# Power.net
KiCad netlist of a schematic drawn in Altium Designer
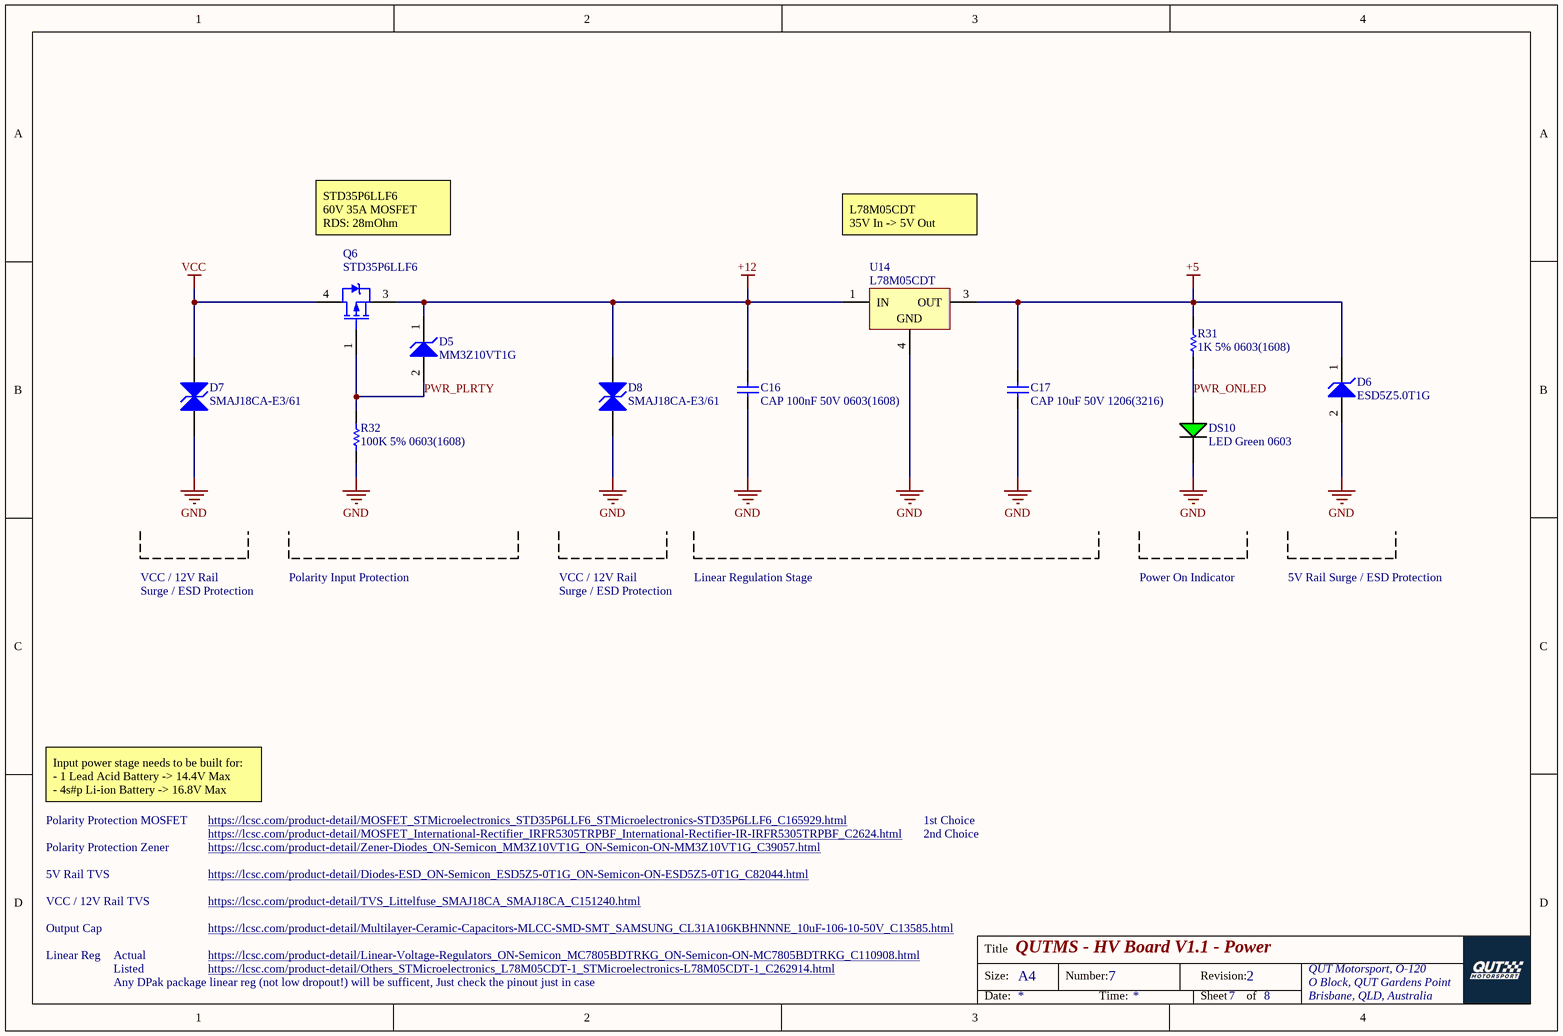
[diagram p0: Power.SchDoc]

(export (version "E")
  (design (tool "Eeschema 10.0.6"))
  (components
    (comp (ref "C16")
      (value "CAP 100nF 50V 0603(1608)")
      (footprint "CAPC0603(1608)100_N")
      (description "CAP 100nF 50V ±5% 0603 (1608 Metric) Thickness 1mm SMD")
      (fields (field (name "TOLERANCE") "Â±5%"))
      (libsource (lib "Altium Content Vault") (part "CAP"))
    )
    (comp (ref "C17")
      (value "CAP 10uF 50V 1206(3216)")
      (footprint "CAPC1206(3216)190_N")
      (description "CAP 10uF 50V ±10% 1206 (3216 Metric) Thickness 1.9mm SMD")
      (fields (field (name "TOLERANCE") "Â±10%"))
      (libsource (lib "Altium Content Vault") (part "CAP"))
    )
    (comp (ref "D5")
      (value "MM3Z10VT1G")
      (footprint "ONSC-SOD-323-2-477-02_V")
      (description "Zener Voltage Regulator, 300 mW, 2-Pin SOD-323, Pb-Free, Tape and Reel")
      (fields (field (name "MANUFACTURER") "On Semiconductor"))
      (libsource (lib "Altium Content Vault") (part "ONSC-K1A2-2"))
    )
    (comp (ref "D6")
      (value "ESD5Z5.0T1G")
      (footprint "ONSC-SOD-523-2-502-01_V")
      (fields (field (name "MANUFACTURER") "On Semiconductor"))
      (libsource (lib "Altium Content Vault") (part "ONSC-K1A2-2"))
    )
    (comp (ref "D7")
      (value "SMAJ18CA-E3/61")
      (footprint "VISH-DO-214AC-2_N")
      (fields (field (name "MANUFACTURER") "Vishay Semiconductor"))
      (libsource (lib "Altium Content Vault") (part "VISH-A1A2-2"))
    )
    (comp (ref "D8")
      (value "SMAJ18CA-E3/61")
      (footprint "VISH-DO-214AC-2_N")
      (fields (field (name "MANUFACTURER") "Vishay Semiconductor"))
      (libsource (lib "Altium Content Vault") (part "VISH-A1A2-2"))
    )
    (comp (ref "DS10")
      (value "LED Green 0603")
      (footprint "LED GREEN 0603")
      (libsource (lib "QUTMS_LEDLibrary") (part "LED GREEN 0603"))
    )
    (comp (ref "Q6")
      (value "STD35P6LLF6")
      (footprint "ONSC-DPAK-3-369C-01_V")
      (description "Power MOSFET, -60 V, -12 A, P-Channel, 3-Pin DPAK, Pb-Free, Tape and Reel")
      (fields (field (name "MANUFACTURER") "On Semiconductor") (field (name "PARTNUMBER") "NTD2955T4G"))
      (libsource (lib "Altium Content Vault") (part "ONSC-PMOS-G1S3D4-3_B"))
    )
    (comp (ref "R31")
      (value "1K 5% 0603(1608)")
      (footprint "RESC0603(1608)_N")
      (description "1K 0.1W 5% 0603 (1608 Metric)  SMD")
      (fields (field (name "TOLERANCE") "5 %") (field (name "POWER") "0.1 W"))
      (libsource (lib "Altium Content Vault") (part "RES"))
    )
    (comp (ref "R32")
      (value "100K 5% 0603(1608)")
      (footprint "RESC0603(1608)_N")
      (description "100K 0.1W 5% 0603 (1608 Metric)  SMD")
      (fields (field (name "TOLERANCE") "5 %") (field (name "POWER") "0.1 W"))
      (libsource (lib "Altium Content Vault") (part "RES"))
    )
    (comp (ref "U14")
      (value "L78M05CDT")
      (footprint "STM-TO252-3_A_V")
      (description "Precision Regulator, 0.5 A, 5 V Output, 0 to 150 degC, 3-Pin DPAK (TO252), RoHS, Tube")
      (fields (field (name "MANUFACTURER") "STMicroelectronics"))
      (libsource (lib "Altium Content Vault") (part "STM-L78M05-TO252-3"))
    )
  )
  (nets
    (net (code "1") (name "+5") (class "Default")
      (node (ref "C17") (pin "2") (pinfunction "2_2") (pintype "passive"))
      (node (ref "D6") (pin "1") (pinfunction "K_1") (pintype "passive"))
      (node (ref "R31") (pin "2") (pinfunction "2_2") (pintype "passive"))
      (node (ref "U14") (pin "3") (pinfunction "OUT_3") (pintype "power_in"))
    )
    (net (code "2") (name "+12") (class "Default")
      (node (ref "C16") (pin "2") (pinfunction "2_2") (pintype "passive"))
      (node (ref "D5") (pin "1") (pinfunction "K_1") (pintype "passive"))
      (node (ref "D8") (pin "2") (pinfunction "A2_2") (pintype "passive"))
      (node (ref "Q6") (pin "3") (pinfunction "S_3") (pintype "passive"))
      (node (ref "U14") (pin "1") (pinfunction "IN_1") (pintype "power_in"))
    )
    (net (code "3") (name "/PWR_ONLED") (class "Default")
      (node (ref "DS10") (pin "1") (pinfunction "A_1") (pintype "passive"))
      (node (ref "R31") (pin "1") (pinfunction "1_1") (pintype "passive"))
    )
    (net (code "4") (name "/PWR_PLRTY") (class "Default")
      (node (ref "D5") (pin "2") (pinfunction "A_2") (pintype "passive"))
      (node (ref "Q6") (pin "1") (pinfunction "G_1") (pintype "passive"))
      (node (ref "R32") (pin "2") (pinfunction "2_2") (pintype "passive"))
    )
    (net (code "5") (name "GND") (class "Default")
      (node (ref "C16") (pin "1") (pinfunction "1_1") (pintype "passive"))
      (node (ref "C17") (pin "1") (pinfunction "1_1") (pintype "passive"))
      (node (ref "D6") (pin "2") (pinfunction "A_2") (pintype "passive"))
      (node (ref "D7") (pin "1") (pinfunction "A1_1") (pintype "passive"))
      (node (ref "D8") (pin "1") (pinfunction "A1_1") (pintype "passive"))
      (node (ref "DS10") (pin "2") (pinfunction "C_2") (pintype "passive"))
      (node (ref "R32") (pin "1") (pinfunction "1_1") (pintype "passive"))
      (node (ref "U14") (pin "4") (pinfunction "GND_4") (pintype "power_in"))
    )
    (net (code "6") (name "VCC") (class "Default")
      (node (ref "D7") (pin "2") (pinfunction "A2_2") (pintype "passive"))
      (node (ref "Q6") (pin "4") (pinfunction "D_4") (pintype "passive"))
    )
  )
)
